# PowerUnit.net
KiCad netlist of a schematic drawn in Altium Designer
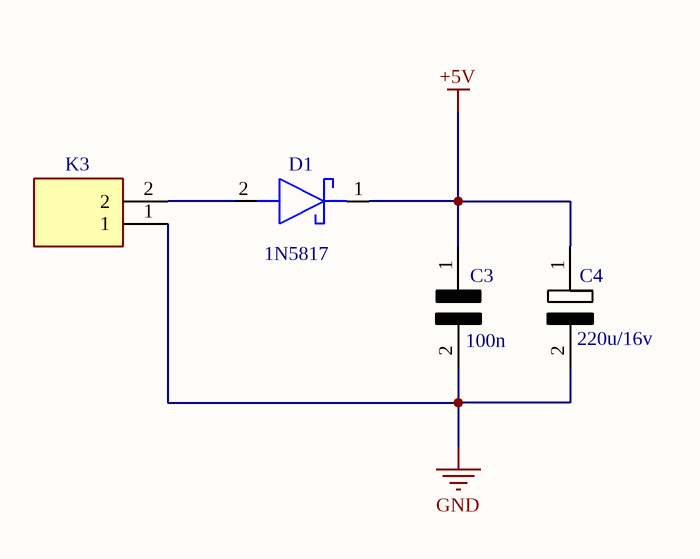
[diagram p0: PowerUnit.SchDoc]

(export (version "E")
  (design (tool "Eeschema 10.0.6"))
  (components
    (comp (ref "C3")
      (value "100n")
      (footprint "C0805")
      (description "0805 ceramic capacitor")
      (fields
        (field (name "MANUFACTURER_PART_NUMBER") "GRM188R71H103KA01D")
        (field (name "MOUSER PART NUMBER") "81-GRM39X103K50D")
      )
      (libsource (lib "Schlib1") (part "KeramischeC0805_1"))
    )
    (comp (ref "C4")
      (value "220u/16v")
      (footprint "C0805")
      (description "0805 ceramic capacitor")
      (fields
        (field (name "MANUFACTURER_PART_NUMBER") "GRM188R71H103KA01D")
        (field (name "MOUSER PART NUMBER") "81-GRM39X103K50D")
      )
      (libsource (lib "Schlib1") (part "elektrolytischeC0805"))
    )
    (comp (ref "D1")
      (value "1N5817")
      (footprint "1n5817_footprint")
      (description "Schottky Diode")
      (libsource (lib "Schlib1") (part "1N5817"))
    )
    (comp (ref "K3")
      (value "Con2Polig")
      (footprint "SamacSys:OSTTE020104")
      (description "Connector")
      (fields (field (name "MANUFACTURER_PART_NUMBER") "OSTTE020104"))
      (libsource (lib "Schlib1") (part "Con2Polig"))
    )
  )
  (nets
    (net (code "1") (name "+5V") (class "Default")
      (node (ref "C3") (pin "1") (pinfunction "1_1") (pintype "passive"))
      (node (ref "C4") (pin "1") (pinfunction "1_1") (pintype "passive"))
      (node (ref "D1") (pin "1") (pinfunction "K_1") (pintype "passive"))
    )
    (net (code "2") (name "GND") (class "Default")
      (node (ref "C3") (pin "2") (pinfunction "2_2") (pintype "passive"))
      (node (ref "C4") (pin "2") (pinfunction "2_2") (pintype "passive"))
      (node (ref "K3") (pin "1") (pinfunction "1_1") (pintype "passive"))
    )
    (net (code "3") (name "Net-(D1-A)") (class "Default")
      (node (ref "D1") (pin "2") (pinfunction "A_2") (pintype "passive"))
      (node (ref "K3") (pin "2") (pinfunction "2_2") (pintype "passive"))
    )
  )
)
